# 50x15.net
KiCad netlist of a schematic drawn in EAGLE
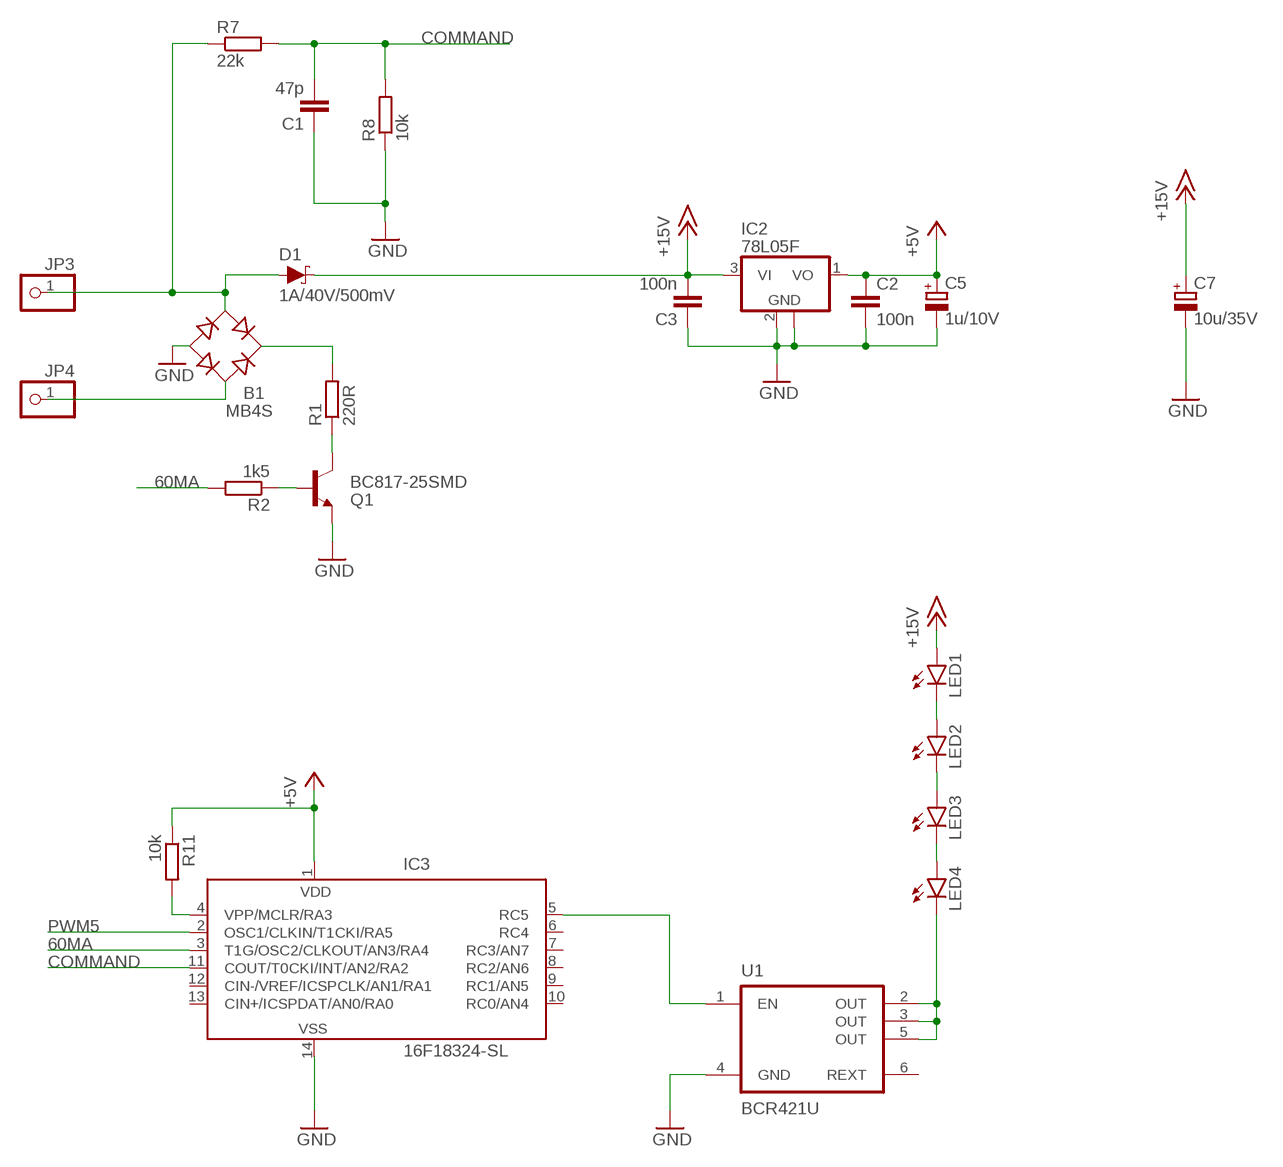
[diagram p0: schematic, sheet 1]

(export (version "E")
  (design (tool "Eeschema 10.0.6"))
  (components
    (comp (ref "B1")
      (value "MB4S")
      (footprint "eagle-import:SOIC-4")
      (libsource (lib "eagle-import") (part "MBS4"))
    )
    (comp (ref "C1")
      (value "47p")
      (footprint "eagle-import:C0805")
      (libsource (lib "eagle-import") (part "C-EUC0805"))
    )
    (comp (ref "C2")
      (value "100n")
      (footprint "eagle-import:C3216")
      (libsource (lib "eagle-import") (part "C-EUC3216"))
    )
    (comp (ref "C3")
      (value "100n")
      (footprint "eagle-import:C3216")
      (libsource (lib "eagle-import") (part "C-EUC3216"))
    )
    (comp (ref "C5")
      (value "1u/10V")
      (footprint "eagle-import:A_3216-18R")
      (libsource (lib "eagle-import") (part "CPOL-EUA/3216-18R"))
    )
    (comp (ref "C7")
      (value "10u/35V")
      (footprint "eagle-import:D_7343-31R")
      (libsource (lib "eagle-import") (part "CPOL-EUD/7343-31R"))
    )
    (comp (ref "D1")
      (value "1A/40V/500mV")
      (footprint "eagle-import:SMA-DIODE")
      (libsource (lib "eagle-import") (part "DIODE-SCHOTTKY-SS14"))
    )
    (comp (ref "IC2")
      (value "78L05F")
      (footprint "eagle-import:SOT89")
      (libsource (lib "eagle-import") (part "78LF05"))
    )
    (comp (ref "IC3")
      (value "16F18324-SL")
      (footprint "eagle-import:SO-14")
      (fields (field (name "MF") "MICROCHIP") (field (name "MPN") "PIC16F676-I/SL"))
      (libsource (lib "eagle-import") (part "PIC16F676SL"))
    )
    (comp (ref "JP3")
      (value "PINHD-1X1")
      (footprint "eagle-import:1X01")
      (libsource (lib "eagle-import") (part "PINHD-1X1"))
    )
    (comp (ref "JP4")
      (value "PINHD-1X1")
      (footprint "eagle-import:1X01")
      (libsource (lib "eagle-import") (part "PINHD-1X1"))
    )
    (comp (ref "LED1")
      (value "LEDKA-3528ASYC")
      (footprint "eagle-import:KA-3528ASYC")
      (libsource (lib "eagle-import") (part "LEDKA-3528ASYC"))
    )
    (comp (ref "LED2")
      (value "LEDKA-3528ASYC")
      (footprint "eagle-import:KA-3528ASYC")
      (libsource (lib "eagle-import") (part "LEDKA-3528ASYC"))
    )
    (comp (ref "LED3")
      (value "LEDKA-3528ASYC")
      (footprint "eagle-import:KA-3528ASYC")
      (libsource (lib "eagle-import") (part "LEDKA-3528ASYC"))
    )
    (comp (ref "LED4")
      (value "LEDKA-3528ASYC")
      (footprint "eagle-import:KA-3528ASYC")
      (libsource (lib "eagle-import") (part "LEDKA-3528ASYC"))
    )
    (comp (ref "Q1")
      (value "BC817-25SMD")
      (footprint "eagle-import:SOT23-BEC")
      (libsource (lib "eagle-import") (part "BC817SMD-25"))
    )
    (comp (ref "R1")
      (value "220R")
      (footprint "eagle-import:R1206")
      (libsource (lib "eagle-import") (part "R-EU_R1206"))
    )
    (comp (ref "R2")
      (value "1k5")
      (footprint "eagle-import:R1206")
      (libsource (lib "eagle-import") (part "R-EU_R1206"))
    )
    (comp (ref "R7")
      (value "22k")
      (footprint "eagle-import:R1206")
      (libsource (lib "eagle-import") (part "R-EU_R1206"))
    )
    (comp (ref "R8")
      (value "10k")
      (footprint "eagle-import:R1206")
      (libsource (lib "eagle-import") (part "R-EU_R1206"))
    )
    (comp (ref "R11")
      (value "10k")
      (footprint "eagle-import:R1206")
      (libsource (lib "eagle-import") (part "R-EU_R1206"))
    )
    (comp (ref "U1")
      (value "BCR421U")
      (footprint "eagle-import:SC74-6")
      (fields (field (name "MF") "Infineon"))
      (libsource (lib "eagle-import") (part "BCR421U"))
    )
  )
  (nets
    (net (code "1") (name "+5V") (class "Default")
      (node (ref "C2") (pin "1") (pinfunction "1_1") (pintype "passive"))
      (node (ref "C5") (pin "+") (pinfunction "+_+") (pintype "passive"))
      (node (ref "IC2") (pin "1") (pinfunction "VO_1") (pintype "passive"))
      (node (ref "IC3") (pin "1") (pinfunction "VDD_1") (pintype "power_in"))
      (node (ref "R11") (pin "1") (pinfunction "1_1") (pintype "passive"))
    )
    (net (code "2") (name "+15V") (class "Default")
      (node (ref "C3") (pin "2") (pinfunction "2_2") (pintype "passive"))
      (node (ref "C7") (pin "+") (pinfunction "+_+") (pintype "passive"))
      (node (ref "D1") (pin "C") (pinfunction "C_C") (pintype "passive"))
      (node (ref "IC2") (pin "3") (pinfunction "VI_3") (pintype "input"))
      (node (ref "LED1") (pin "A") (pinfunction "A_A") (pintype "passive"))
    )
    (net (code "3") (name "/60MA") (class "Default")
      (node (ref "IC3") (pin "3") (pinfunction "T1G/OSC2/CLKOUT/AN3/RA4_3") (pintype "bidirectional"))
      (node (ref "R2") (pin "2") (pinfunction "2_2") (pintype "passive"))
    )
    (net (code "4") (name "/COMMAND") (class "Default")
      (node (ref "C1") (pin "2") (pinfunction "2_2") (pintype "passive"))
      (node (ref "IC3") (pin "11") (pinfunction "COUT/T0CKI/INT/AN2/RA2_11") (pintype "bidirectional"))
      (node (ref "R7") (pin "2") (pinfunction "2_2") (pintype "passive"))
      (node (ref "R8") (pin "2") (pinfunction "2_2") (pintype "passive"))
    )
    (net (code "5") (name "/PWM5") (class "Default")
      (node (ref "IC3") (pin "2") (pinfunction "OSC1/CLKIN/T1CKI/RA5_2") (pintype "bidirectional"))
    )
    (net (code "6") (name "GND") (class "Default")
      (node (ref "B1") (pin "-") (pinfunction "-_-") (pintype "passive"))
      (node (ref "C1") (pin "1") (pinfunction "1_1") (pintype "passive"))
      (node (ref "C2") (pin "2") (pinfunction "2_2") (pintype "passive"))
      (node (ref "C3") (pin "1") (pinfunction "1_1") (pintype "passive"))
      (node (ref "C5") (pin "-") (pinfunction "-_-") (pintype "passive"))
      (node (ref "C7") (pin "-") (pinfunction "-_-") (pintype "passive"))
      (node (ref "IC2") (pin "2") (pinfunction "GND_2") (pintype "passive"))
      (node (ref "IC2") (pin "2@1") (pinfunction "GND_2@1") (pintype "passive"))
      (node (ref "IC3") (pin "14") (pinfunction "VSS_14") (pintype "power_in"))
      (node (ref "Q1") (pin "E") (pinfunction "E_E") (pintype "passive"))
      (node (ref "R8") (pin "1") (pinfunction "1_1") (pintype "passive"))
      (node (ref "U1") (pin "4") (pinfunction "GND_4") (pintype "input"))
    )
    (net (code "7") (name "Net-(B1-AC1)") (class "Default")
      (node (ref "B1") (pin "~1") (pinfunction "AC1_~1") (pintype "passive"))
      (node (ref "D1") (pin "A") (pinfunction "A_A") (pintype "passive"))
      (node (ref "JP3") (pin "1") (pinfunction "1_1") (pintype "passive"))
      (node (ref "R7") (pin "1") (pinfunction "1_1") (pintype "passive"))
    )
    (net (code "8") (name "Net-(B1-AC2)") (class "Default")
      (node (ref "B1") (pin "~2") (pinfunction "AC2_~2") (pintype "passive"))
      (node (ref "JP4") (pin "1") (pinfunction "1_1") (pintype "passive"))
    )
    (net (code "9") (name "Net-(B1-Pad+)") (class "Default")
      (node (ref "B1") (pin "+") (pinfunction "+_+") (pintype "passive"))
      (node (ref "R1") (pin "2") (pinfunction "2_2") (pintype "passive"))
    )
    (net (code "10") (name "Net-(IC3-RC5)") (class "Default")
      (node (ref "IC3") (pin "5") (pinfunction "RC5_5") (pintype "bidirectional"))
      (node (ref "U1") (pin "1") (pinfunction "EN_1") (pintype "input"))
    )
    (net (code "11") (name "Net-(IC3-VPP{slash}MCLR{slash}RA3)") (class "Default")
      (node (ref "IC3") (pin "4") (pinfunction "VPP/MCLR/RA3_4") (pintype "input"))
      (node (ref "R11") (pin "2") (pinfunction "2_2") (pintype "passive"))
    )
    (net (code "12") (name "Net-(LED1-PadC)") (class "Default")
      (node (ref "LED1") (pin "C") (pinfunction "C_C") (pintype "passive"))
      (node (ref "LED2") (pin "A") (pinfunction "A_A") (pintype "passive"))
    )
    (net (code "13") (name "Net-(LED2-PadC)") (class "Default")
      (node (ref "LED2") (pin "C") (pinfunction "C_C") (pintype "passive"))
      (node (ref "LED3") (pin "A") (pinfunction "A_A") (pintype "passive"))
    )
    (net (code "14") (name "Net-(LED3-PadC)") (class "Default")
      (node (ref "LED3") (pin "C") (pinfunction "C_C") (pintype "passive"))
      (node (ref "LED4") (pin "A") (pinfunction "A_A") (pintype "passive"))
    )
    (net (code "15") (name "Net-(LED4-PadC)") (class "Default")
      (node (ref "LED4") (pin "C") (pinfunction "C_C") (pintype "passive"))
      (node (ref "U1") (pin "2") (pinfunction "OUT_2") (pintype "open_collector"))
      (node (ref "U1") (pin "3") (pinfunction "OUT_3") (pintype "open_collector"))
      (node (ref "U1") (pin "5") (pinfunction "OUT_5") (pintype "open_collector"))
    )
    (net (code "16") (name "Net-(Q1-PadB)") (class "Default")
      (node (ref "Q1") (pin "B") (pinfunction "B_B") (pintype "passive"))
      (node (ref "R2") (pin "1") (pinfunction "1_1") (pintype "passive"))
    )
    (net (code "17") (name "Net-(Q1-PadC)") (class "Default")
      (node (ref "Q1") (pin "C") (pinfunction "C_C") (pintype "passive"))
      (node (ref "R1") (pin "1") (pinfunction "1_1") (pintype "passive"))
    )
    (net (code "18") (name "unconnected-(IC3-CIN+{slash}ICSPDAT{slash}AN0{slash}RA0-Pad13)") (class "Default")
      (node (ref "IC3") (pin "13") (pinfunction "CIN+/ICSPDAT/AN0/RA0_13") (pintype "bidirectional"))
    )
    (net (code "19") (name "unconnected-(IC3-CIN-{slash}VREF{slash}ICSPCLK{slash}AN1{slash}RA1-Pad12)") (class "Default")
      (node (ref "IC3") (pin "12") (pinfunction "CIN-/VREF/ICSPCLK/AN1/RA1_12") (pintype "bidirectional"))
    )
    (net (code "20") (name "unconnected-(IC3-RC0{slash}AN4-Pad10)") (class "Default")
      (node (ref "IC3") (pin "10") (pinfunction "RC0/AN4_10") (pintype "bidirectional"))
    )
    (net (code "21") (name "unconnected-(IC3-RC1{slash}AN5-Pad9)") (class "Default")
      (node (ref "IC3") (pin "9") (pinfunction "RC1/AN5_9") (pintype "bidirectional"))
    )
    (net (code "22") (name "unconnected-(IC3-RC2{slash}AN6-Pad8)") (class "Default")
      (node (ref "IC3") (pin "8") (pinfunction "RC2/AN6_8") (pintype "bidirectional"))
    )
    (net (code "23") (name "unconnected-(IC3-RC3{slash}AN7-Pad7)") (class "Default")
      (node (ref "IC3") (pin "7") (pinfunction "RC3/AN7_7") (pintype "bidirectional"))
    )
    (net (code "24") (name "unconnected-(IC3-RC4-Pad6)") (class "Default")
      (node (ref "IC3") (pin "6") (pinfunction "RC4_6") (pintype "bidirectional"))
    )
    (net (code "25") (name "unconnected-(U1-REXT-Pad6)") (class "Default")
      (node (ref "U1") (pin "6") (pinfunction "REXT_6") (pintype "bidirectional"))
    )
  )
)
